# led_quadcoopter.net
KiCad netlist of a schematic drawn in EAGLE
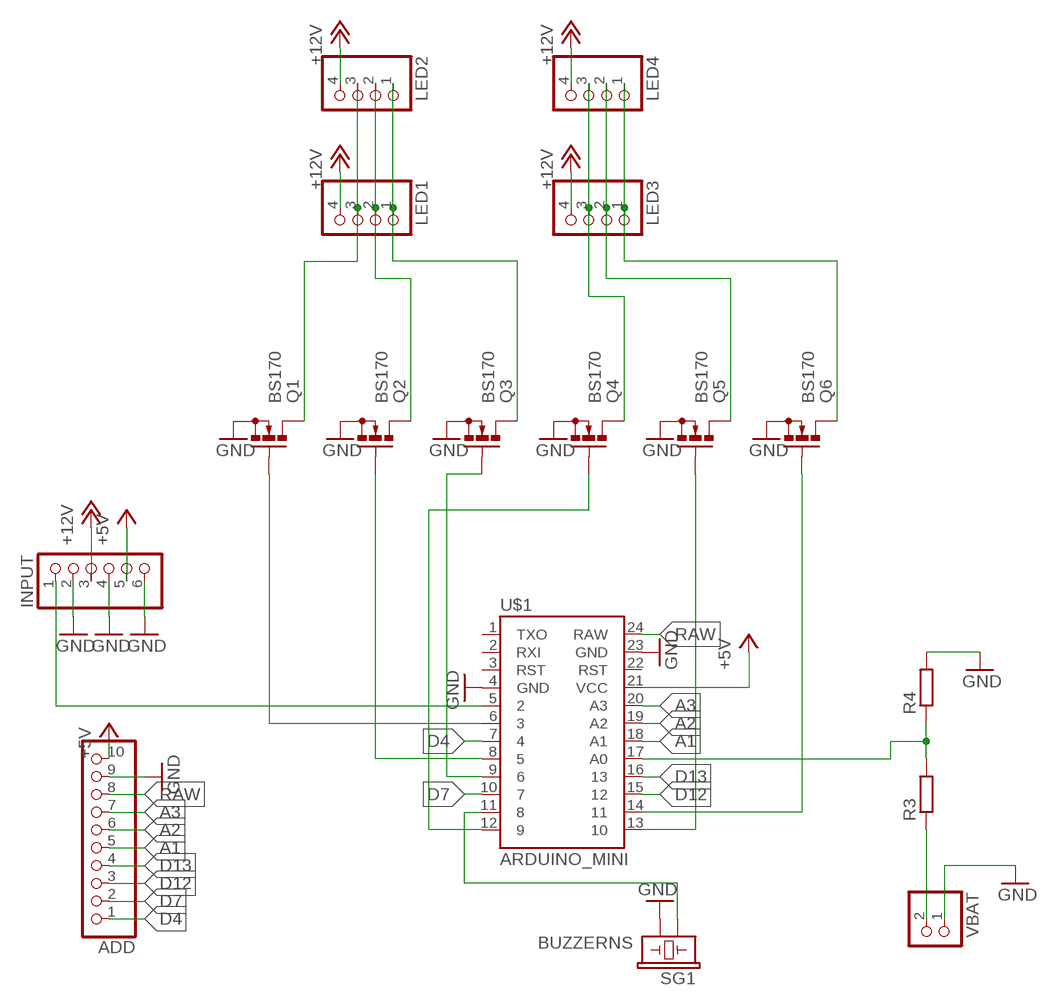
[diagram p0: schematic, sheet 1]

(export (version "E")
  (design (tool "Eeschema 10.0.6"))
  (components
    (comp (ref "ADD")
      (value "PINHD-1X10")
      (footprint "eagle-import:1X10")
      (libsource (lib "eagle-import") (part "PINHD-1X10"))
    )
    (comp (ref "INPUT")
      (value "PINHD-1X6")
      (footprint "eagle-import:1X06")
      (libsource (lib "eagle-import") (part "PINHD-1X6"))
    )
    (comp (ref "LED1")
      (value "PINHD-1X4")
      (footprint "eagle-import:1X04")
      (libsource (lib "eagle-import") (part "PINHD-1X4"))
    )
    (comp (ref "LED2")
      (value "PINHD-1X4")
      (footprint "eagle-import:1X04")
      (libsource (lib "eagle-import") (part "PINHD-1X4"))
    )
    (comp (ref "LED3")
      (value "PINHD-1X4")
      (footprint "eagle-import:1X04")
      (libsource (lib "eagle-import") (part "PINHD-1X4"))
    )
    (comp (ref "LED4")
      (value "PINHD-1X4")
      (footprint "eagle-import:1X04")
      (libsource (lib "eagle-import") (part "PINHD-1X4"))
    )
    (comp (ref "Q1")
      (value "BS170")
      (footprint "eagle-import:SOT54E")
      (libsource (lib "eagle-import") (part "BS170"))
    )
    (comp (ref "Q2")
      (value "BS170")
      (footprint "eagle-import:SOT54E")
      (libsource (lib "eagle-import") (part "BS170"))
    )
    (comp (ref "Q3")
      (value "BS170")
      (footprint "eagle-import:SOT54E")
      (libsource (lib "eagle-import") (part "BS170"))
    )
    (comp (ref "Q4")
      (value "BS170")
      (footprint "eagle-import:SOT54E")
      (libsource (lib "eagle-import") (part "BS170"))
    )
    (comp (ref "Q5")
      (value "BS170")
      (footprint "eagle-import:SOT54E")
      (libsource (lib "eagle-import") (part "BS170"))
    )
    (comp (ref "Q6")
      (value "BS170")
      (footprint "eagle-import:SOT54E")
      (libsource (lib "eagle-import") (part "BS170"))
    )
    (comp (ref "R3")
      (value "R-EU_0207/10")
      (footprint "eagle-import:0207_10")
      (libsource (lib "eagle-import") (part "R-EU_0207/10"))
    )
    (comp (ref "R4")
      (value "R-EU_0207/10")
      (footprint "eagle-import:0207_10")
      (libsource (lib "eagle-import") (part "R-EU_0207/10"))
    )
    (comp (ref "SG1")
      (value "BUZZERNS")
      (footprint "eagle-import:BUZZER-12MM-NS")
      (libsource (lib "eagle-import") (part "BUZZERNS"))
    )
    (comp (ref "U$1")
      (value "ARDUINO_MINI")
      (footprint "eagle-import:ARDUINO_MINI")
      (libsource (lib "eagle-import") (part "ARDUINO_MINI"))
    )
    (comp (ref "VBAT")
      (value "PINHD-1X2")
      (footprint "eagle-import:1X02")
      (libsource (lib "eagle-import") (part "PINHD-1X2"))
    )
  )
  (nets
    (net (code "1") (name "+5V") (class "Default")
      (node (ref "ADD") (pin "10") (pinfunction "10_10") (pintype "passive"))
      (node (ref "INPUT") (pin "5") (pinfunction "5_5") (pintype "passive"))
      (node (ref "U$1") (pin "21") (pinfunction "VCC_21") (pintype "bidirectional"))
    )
    (net (code "2") (name "+12V") (class "Default")
      (node (ref "INPUT") (pin "3") (pinfunction "3_3") (pintype "passive"))
      (node (ref "LED1") (pin "4") (pinfunction "4_4") (pintype "passive"))
      (node (ref "LED2") (pin "4") (pinfunction "4_4") (pintype "passive"))
      (node (ref "LED3") (pin "4") (pinfunction "4_4") (pintype "passive"))
      (node (ref "LED4") (pin "4") (pinfunction "4_4") (pintype "passive"))
    )
    (net (code "3") (name "A1") (class "Default")
      (node (ref "ADD") (pin "5") (pinfunction "5_5") (pintype "passive"))
      (node (ref "U$1") (pin "18") (pinfunction "A1_18") (pintype "bidirectional"))
    )
    (net (code "4") (name "A2") (class "Default")
      (node (ref "ADD") (pin "6") (pinfunction "6_6") (pintype "passive"))
      (node (ref "U$1") (pin "19") (pinfunction "A2_19") (pintype "bidirectional"))
    )
    (net (code "5") (name "A3") (class "Default")
      (node (ref "ADD") (pin "7") (pinfunction "7_7") (pintype "passive"))
      (node (ref "U$1") (pin "20") (pinfunction "A3_20") (pintype "bidirectional"))
    )
    (net (code "6") (name "D4") (class "Default")
      (node (ref "ADD") (pin "1") (pinfunction "1_1") (pintype "passive"))
      (node (ref "U$1") (pin "7") (pinfunction "4_7") (pintype "bidirectional"))
    )
    (net (code "7") (name "D7") (class "Default")
      (node (ref "ADD") (pin "2") (pinfunction "2_2") (pintype "passive"))
      (node (ref "U$1") (pin "10") (pinfunction "7_10") (pintype "bidirectional"))
    )
    (net (code "8") (name "D12") (class "Default")
      (node (ref "ADD") (pin "3") (pinfunction "3_3") (pintype "passive"))
      (node (ref "U$1") (pin "15") (pinfunction "12_15") (pintype "bidirectional"))
    )
    (net (code "9") (name "D13") (class "Default")
      (node (ref "ADD") (pin "4") (pinfunction "4_4") (pintype "passive"))
      (node (ref "U$1") (pin "16") (pinfunction "13_16") (pintype "bidirectional"))
    )
    (net (code "10") (name "GND") (class "Default")
      (node (ref "ADD") (pin "9") (pinfunction "9_9") (pintype "passive"))
      (node (ref "INPUT") (pin "2") (pinfunction "2_2") (pintype "passive"))
      (node (ref "INPUT") (pin "4") (pinfunction "4_4") (pintype "passive"))
      (node (ref "INPUT") (pin "6") (pinfunction "6_6") (pintype "passive"))
      (node (ref "Q1") (pin "S") (pinfunction "S_S") (pintype "passive"))
      (node (ref "Q2") (pin "S") (pinfunction "S_S") (pintype "passive"))
      (node (ref "Q3") (pin "S") (pinfunction "S_S") (pintype "passive"))
      (node (ref "Q4") (pin "S") (pinfunction "S_S") (pintype "passive"))
      (node (ref "Q5") (pin "S") (pinfunction "S_S") (pintype "passive"))
      (node (ref "Q6") (pin "S") (pinfunction "S_S") (pintype "passive"))
      (node (ref "R4") (pin "2") (pinfunction "2_2") (pintype "passive"))
      (node (ref "SG1") (pin "-") (pinfunction "2_-") (pintype "passive"))
      (node (ref "U$1") (pin "23") (pinfunction "GND_23") (pintype "bidirectional"))
      (node (ref "U$1") (pin "4") (pinfunction "GND_4") (pintype "bidirectional"))
      (node (ref "VBAT") (pin "1") (pinfunction "1_1") (pintype "passive"))
    )
    (net (code "11") (name "Net-(LED1-Pad1)") (class "Default")
      (node (ref "LED1") (pin "1") (pinfunction "1_1") (pintype "passive"))
      (node (ref "LED2") (pin "1") (pinfunction "1_1") (pintype "passive"))
      (node (ref "Q3") (pin "D") (pinfunction "D_D") (pintype "passive"))
    )
    (net (code "12") (name "Net-(LED1-Pad2)") (class "Default")
      (node (ref "LED1") (pin "2") (pinfunction "2_2") (pintype "passive"))
      (node (ref "LED2") (pin "2") (pinfunction "2_2") (pintype "passive"))
      (node (ref "Q2") (pin "D") (pinfunction "D_D") (pintype "passive"))
    )
    (net (code "13") (name "Net-(LED1-Pad3)") (class "Default")
      (node (ref "LED1") (pin "3") (pinfunction "3_3") (pintype "passive"))
      (node (ref "LED2") (pin "3") (pinfunction "3_3") (pintype "passive"))
      (node (ref "Q1") (pin "D") (pinfunction "D_D") (pintype "passive"))
    )
    (net (code "14") (name "Net-(LED3-Pad1)") (class "Default")
      (node (ref "LED3") (pin "1") (pinfunction "1_1") (pintype "passive"))
      (node (ref "LED4") (pin "1") (pinfunction "1_1") (pintype "passive"))
      (node (ref "Q6") (pin "D") (pinfunction "D_D") (pintype "passive"))
    )
    (net (code "15") (name "Net-(LED3-Pad2)") (class "Default")
      (node (ref "LED3") (pin "2") (pinfunction "2_2") (pintype "passive"))
      (node (ref "LED4") (pin "2") (pinfunction "2_2") (pintype "passive"))
      (node (ref "Q5") (pin "D") (pinfunction "D_D") (pintype "passive"))
    )
    (net (code "16") (name "Net-(LED3-Pad3)") (class "Default")
      (node (ref "LED3") (pin "3") (pinfunction "3_3") (pintype "passive"))
      (node (ref "LED4") (pin "3") (pinfunction "3_3") (pintype "passive"))
      (node (ref "Q4") (pin "D") (pinfunction "D_D") (pintype "passive"))
    )
    (net (code "17") (name "Net-(R3-Pad1)") (class "Default")
      (node (ref "R3") (pin "1") (pinfunction "1_1") (pintype "passive"))
      (node (ref "VBAT") (pin "2") (pinfunction "2_2") (pintype "passive"))
    )
    (net (code "18") (name "Net-(SG1-1)") (class "Default")
      (node (ref "SG1") (pin "+") (pinfunction "1_+") (pintype "passive"))
      (node (ref "U$1") (pin "11") (pinfunction "8_11") (pintype "bidirectional"))
    )
    (net (code "19") (name "Net-(U$1-2)") (class "Default")
      (node (ref "INPUT") (pin "1") (pinfunction "1_1") (pintype "passive"))
      (node (ref "U$1") (pin "5") (pinfunction "2_5") (pintype "bidirectional"))
    )
    (net (code "20") (name "Net-(U$1-3)") (class "Default")
      (node (ref "Q1") (pin "G") (pinfunction "G_G") (pintype "passive"))
      (node (ref "U$1") (pin "6") (pinfunction "3_6") (pintype "bidirectional"))
    )
    (net (code "21") (name "Net-(U$1-5)") (class "Default")
      (node (ref "Q2") (pin "G") (pinfunction "G_G") (pintype "passive"))
      (node (ref "U$1") (pin "8") (pinfunction "5_8") (pintype "bidirectional"))
    )
    (net (code "22") (name "Net-(U$1-6)") (class "Default")
      (node (ref "Q3") (pin "G") (pinfunction "G_G") (pintype "passive"))
      (node (ref "U$1") (pin "9") (pinfunction "6_9") (pintype "bidirectional"))
    )
    (net (code "23") (name "Net-(U$1-9)") (class "Default")
      (node (ref "Q4") (pin "G") (pinfunction "G_G") (pintype "passive"))
      (node (ref "U$1") (pin "12") (pinfunction "9_12") (pintype "bidirectional"))
    )
    (net (code "24") (name "Net-(U$1-10)") (class "Default")
      (node (ref "Q5") (pin "G") (pinfunction "G_G") (pintype "passive"))
      (node (ref "U$1") (pin "13") (pinfunction "10_13") (pintype "bidirectional"))
    )
    (net (code "25") (name "Net-(U$1-11)") (class "Default")
      (node (ref "Q6") (pin "G") (pinfunction "G_G") (pintype "passive"))
      (node (ref "U$1") (pin "14") (pinfunction "11_14") (pintype "bidirectional"))
    )
    (net (code "26") (name "Net-(U$1-A0)") (class "Default")
      (node (ref "R3") (pin "2") (pinfunction "2_2") (pintype "passive"))
      (node (ref "R4") (pin "1") (pinfunction "1_1") (pintype "passive"))
      (node (ref "U$1") (pin "17") (pinfunction "A0_17") (pintype "bidirectional"))
    )
    (net (code "27") (name "RAW") (class "Default")
      (node (ref "ADD") (pin "8") (pinfunction "8_8") (pintype "passive"))
      (node (ref "U$1") (pin "24") (pinfunction "RAW_24") (pintype "bidirectional"))
    )
    (net (code "28") (name "unconnected-(U$1-RST-Pad3)") (class "Default")
      (node (ref "U$1") (pin "3") (pinfunction "RST_3") (pintype "bidirectional"))
    )
    (net (code "29") (name "unconnected-(U$1-RST-Pad22)") (class "Default")
      (node (ref "U$1") (pin "22") (pinfunction "RST_22") (pintype "bidirectional"))
    )
    (net (code "30") (name "unconnected-(U$1-RXI-Pad2)") (class "Default")
      (node (ref "U$1") (pin "2") (pinfunction "RXI_2") (pintype "bidirectional"))
    )
    (net (code "31") (name "unconnected-(U$1-TXO-Pad1)") (class "Default")
      (node (ref "U$1") (pin "1") (pinfunction "TXO_1") (pintype "bidirectional"))
    )
  )
)
